# vds_topboard_beaglebone_revA.net
KiCad netlist of a schematic drawn in EAGLE
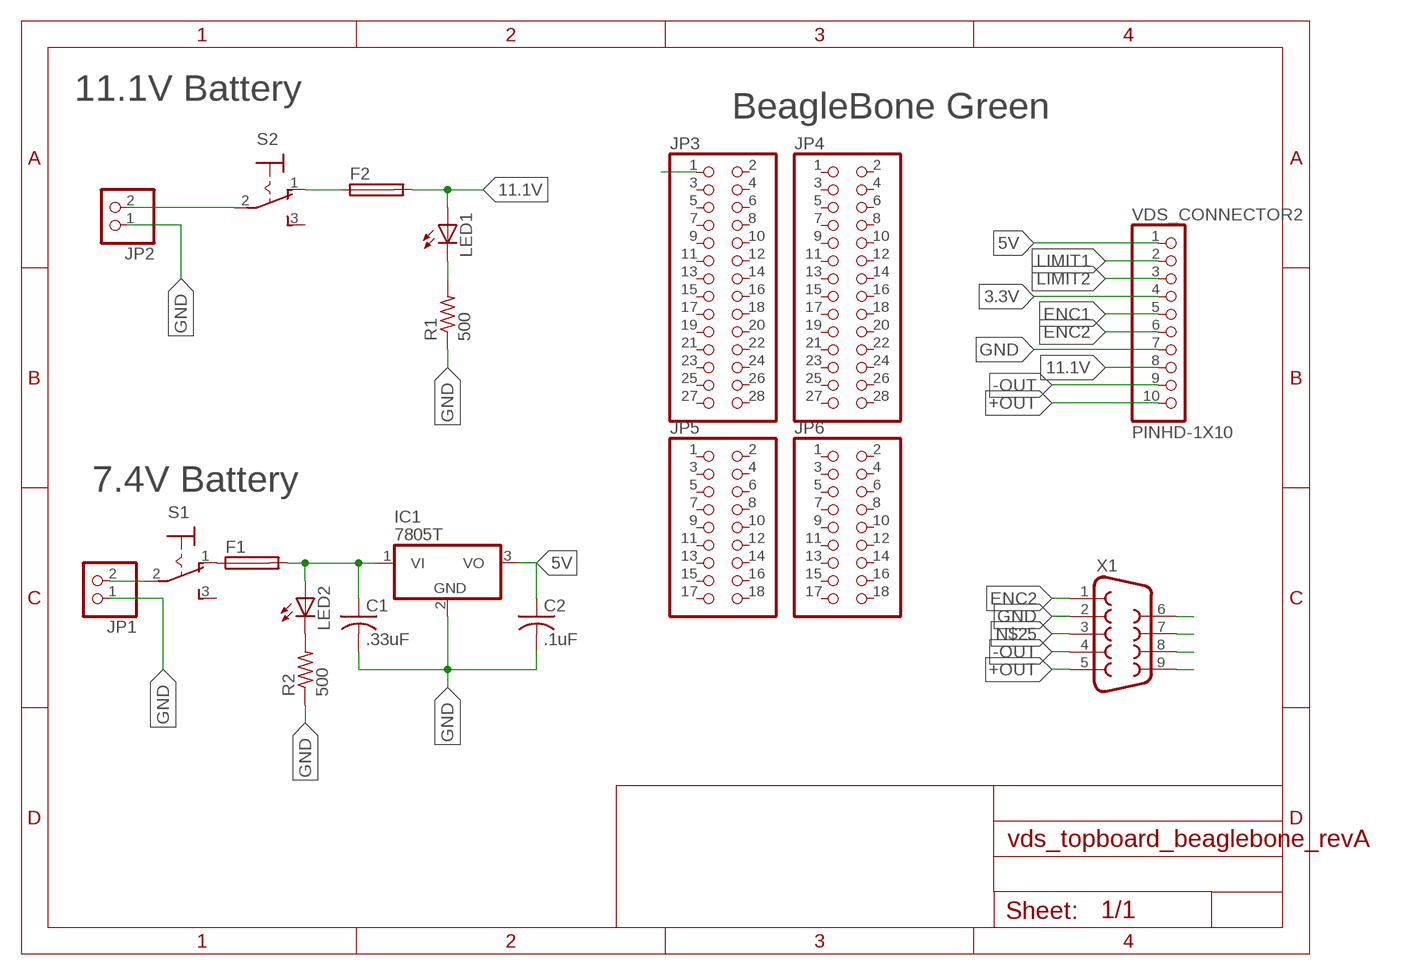
[diagram p0: schematic, sheet 1]

(export (version "E")
  (design (tool "Eeschema 10.0.6"))
  (components
    (comp (ref "C1")
      (value ".33uF")
      (footprint "eagle-import:C025-030X050")
      (libsource (lib "eagle-import") (part "C-US025-030X050"))
    )
    (comp (ref "C2")
      (value ".1uF")
      (footprint "eagle-import:C025-030X050")
      (libsource (lib "eagle-import") (part "C-US025-030X050"))
    )
    (comp (ref "F1")
      (value "SH22,5")
      (footprint "eagle-import:SH22,5")
      (fields (field (name "MF") "SCHURTER") (field (name "MPN") "0031.8201"))
      (libsource (lib "eagle-import") (part "SH22,5"))
    )
    (comp (ref "F2")
      (value "SH22,5")
      (footprint "eagle-import:SH22,5")
      (fields (field (name "MF") "SCHURTER") (field (name "MPN") "0031.8201"))
      (libsource (lib "eagle-import") (part "SH22,5"))
    )
    (comp (ref "IC1")
      (value "7805T")
      (footprint "eagle-import:TO220H")
      (libsource (lib "eagle-import") (part "78T05"))
    )
    (comp (ref "JP1")
      (value "PINHD-1X2")
      (footprint "eagle-import:1X02")
      (libsource (lib "eagle-import") (part "PINHD-1X2"))
    )
    (comp (ref "JP2")
      (value "PINHD-1X2")
      (footprint "eagle-import:1X02")
      (libsource (lib "eagle-import") (part "PINHD-1X2"))
    )
    (comp (ref "JP3")
      (value "PINHD-2X14")
      (footprint "eagle-import:2X14")
      (libsource (lib "eagle-import") (part "PINHD-2X14"))
    )
    (comp (ref "JP4")
      (value "PINHD-2X14")
      (footprint "eagle-import:2X14")
      (libsource (lib "eagle-import") (part "PINHD-2X14"))
    )
    (comp (ref "JP5")
      (value "PINHD-2X9-BIG")
      (footprint "eagle-import:2X09-BIG")
      (libsource (lib "eagle-import") (part "PINHD-2X9-BIG"))
    )
    (comp (ref "JP6")
      (value "PINHD-2X9-BIG")
      (footprint "eagle-import:2X09-BIG")
      (libsource (lib "eagle-import") (part "PINHD-2X9-BIG"))
    )
    (comp (ref "LED1")
      (value "LED5MM")
      (footprint "eagle-import:LED5MM")
      (libsource (lib "eagle-import") (part "LED5MM"))
    )
    (comp (ref "LED2")
      (value "LED5MM")
      (footprint "eagle-import:LED5MM")
      (libsource (lib "eagle-import") (part "LED5MM"))
    )
    (comp (ref "R1")
      (value "500")
      (footprint "eagle-import:0204_5")
      (libsource (lib "eagle-import") (part "R-US_0204/5"))
    )
    (comp (ref "R2")
      (value "500")
      (footprint "eagle-import:0204_5")
      (libsource (lib "eagle-import") (part "R-US_0204/5"))
    )
    (comp (ref "S1")
      (value "320-916")
      (footprint "eagle-import:320-916")
      (libsource (lib "eagle-import") (part "320-916"))
    )
    (comp (ref "S2")
      (value "320-916")
      (footprint "eagle-import:320-916")
      (libsource (lib "eagle-import") (part "320-916"))
    )
    (comp (ref "VDS_CONNECTOR2")
      (value "PINHD-1X10")
      (footprint "eagle-import:1X10-BIG")
      (libsource (lib "eagle-import") (part "PINHD-1X10"))
    )
    (comp (ref "X1")
      (value "F09VP")
      (footprint "eagle-import:F09VP")
      (libsource (lib "eagle-import") (part "F09VP"))
    )
  )
  (nets
    (net (code "1") (name "+OUT") (class "Default")
      (node (ref "VDS_CONNECTOR2") (pin "10") (pinfunction "10_10") (pintype "passive"))
      (node (ref "X1") (pin "5") (pinfunction "5_5") (pintype "passive"))
    )
    (net (code "2") (name "-OUT") (class "Default")
      (node (ref "VDS_CONNECTOR2") (pin "9") (pinfunction "9_9") (pintype "passive"))
      (node (ref "X1") (pin "4") (pinfunction "4_4") (pintype "passive"))
    )
    (net (code "3") (name "3.3V") (class "Default")
      (node (ref "VDS_CONNECTOR2") (pin "4") (pinfunction "4_4") (pintype "passive"))
      (node (ref "X1") (pin "7") (pinfunction "7_7") (pintype "passive"))
    )
    (net (code "4") (name "5V") (class "Default")
      (node (ref "C2") (pin "1") (pinfunction "1_1") (pintype "passive"))
      (node (ref "IC1") (pin "3") (pinfunction "VO_3") (pintype "passive"))
      (node (ref "VDS_CONNECTOR2") (pin "1") (pinfunction "1_1") (pintype "passive"))
    )
    (net (code "5") (name "11.1V") (class "Default")
      (node (ref "F2") (pin "2") (pinfunction "2_2") (pintype "passive"))
      (node (ref "LED1") (pin "A") (pinfunction "A_A") (pintype "passive"))
      (node (ref "VDS_CONNECTOR2") (pin "8") (pinfunction "8_8") (pintype "passive"))
    )
    (net (code "6") (name "ENC1") (class "Default")
      (node (ref "VDS_CONNECTOR2") (pin "5") (pinfunction "5_5") (pintype "passive"))
      (node (ref "X1") (pin "6") (pinfunction "6_6") (pintype "passive"))
    )
    (net (code "7") (name "ENC2") (class "Default")
      (node (ref "VDS_CONNECTOR2") (pin "6") (pinfunction "6_6") (pintype "passive"))
      (node (ref "X1") (pin "1") (pinfunction "1_1") (pintype "passive"))
    )
    (net (code "8") (name "GND") (class "Default")
      (node (ref "C1") (pin "2") (pinfunction "2_2") (pintype "passive"))
      (node (ref "C2") (pin "2") (pinfunction "2_2") (pintype "passive"))
      (node (ref "IC1") (pin "2") (pinfunction "GND_2") (pintype "passive"))
      (node (ref "JP1") (pin "1") (pinfunction "1_1") (pintype "passive"))
      (node (ref "JP2") (pin "1") (pinfunction "1_1") (pintype "passive"))
      (node (ref "JP3") (pin "1") (pinfunction "1_1") (pintype "passive"))
      (node (ref "R1") (pin "1") (pinfunction "1_1") (pintype "passive"))
      (node (ref "R2") (pin "1") (pinfunction "1_1") (pintype "passive"))
      (node (ref "VDS_CONNECTOR2") (pin "7") (pinfunction "7_7") (pintype "passive"))
      (node (ref "X1") (pin "2") (pinfunction "2_2") (pintype "passive"))
    )
    (net (code "9") (name "LIMIT1") (class "Default")
      (node (ref "VDS_CONNECTOR2") (pin "2") (pinfunction "2_2") (pintype "passive"))
      (node (ref "X1") (pin "9") (pinfunction "9_9") (pintype "passive"))
    )
    (net (code "10") (name "LIMIT2") (class "Default")
      (node (ref "VDS_CONNECTOR2") (pin "3") (pinfunction "3_3") (pintype "passive"))
      (node (ref "X1") (pin "8") (pinfunction "8_8") (pintype "passive"))
    )
    (net (code "11") (name "N$25") (class "Default")
      (node (ref "X1") (pin "3") (pinfunction "3_3") (pintype "passive"))
    )
    (net (code "12") (name "Net-(IC1-VI)") (class "Default")
      (node (ref "C1") (pin "1") (pinfunction "1_1") (pintype "passive"))
      (node (ref "F1") (pin "2") (pinfunction "2_2") (pintype "passive"))
      (node (ref "IC1") (pin "1") (pinfunction "VI_1") (pintype "input"))
      (node (ref "LED2") (pin "A") (pinfunction "A_A") (pintype "passive"))
    )
    (net (code "13") (name "Net-(LED1-C)") (class "Default")
      (node (ref "LED1") (pin "K") (pinfunction "C_K") (pintype "passive"))
      (node (ref "R1") (pin "2") (pinfunction "2_2") (pintype "passive"))
    )
    (net (code "14") (name "Net-(LED2-C)") (class "Default")
      (node (ref "LED2") (pin "K") (pinfunction "C_K") (pintype "passive"))
      (node (ref "R2") (pin "2") (pinfunction "2_2") (pintype "passive"))
    )
    (net (code "15") (name "Net-(S1-O)") (class "Default")
      (node (ref "F1") (pin "1") (pinfunction "1_1") (pintype "passive"))
      (node (ref "S1") (pin "1") (pinfunction "O_1") (pintype "passive"))
    )
    (net (code "16") (name "Net-(S1-P)") (class "Default")
      (node (ref "JP1") (pin "2") (pinfunction "2_2") (pintype "passive"))
      (node (ref "S1") (pin "2") (pinfunction "P_2") (pintype "passive"))
    )
    (net (code "17") (name "Net-(S2-O)") (class "Default")
      (node (ref "F2") (pin "1") (pinfunction "1_1") (pintype "passive"))
      (node (ref "S2") (pin "1") (pinfunction "O_1") (pintype "passive"))
    )
    (net (code "18") (name "Net-(S2-P)") (class "Default")
      (node (ref "JP2") (pin "2") (pinfunction "2_2") (pintype "passive"))
      (node (ref "S2") (pin "2") (pinfunction "P_2") (pintype "passive"))
    )
    (net (code "19") (name "unconnected-(JP3-Pad2)") (class "Default")
      (node (ref "JP3") (pin "2") (pinfunction "2_2") (pintype "passive"))
    )
    (net (code "20") (name "unconnected-(JP3-Pad3)") (class "Default")
      (node (ref "JP3") (pin "3") (pinfunction "3_3") (pintype "passive"))
    )
    (net (code "21") (name "unconnected-(JP3-Pad4)") (class "Default")
      (node (ref "JP3") (pin "4") (pinfunction "4_4") (pintype "passive"))
    )
    (net (code "22") (name "unconnected-(JP3-Pad5)") (class "Default")
      (node (ref "JP3") (pin "5") (pinfunction "5_5") (pintype "passive"))
    )
    (net (code "23") (name "unconnected-(JP3-Pad6)") (class "Default")
      (node (ref "JP3") (pin "6") (pinfunction "6_6") (pintype "passive"))
    )
    (net (code "24") (name "unconnected-(JP3-Pad7)") (class "Default")
      (node (ref "JP3") (pin "7") (pinfunction "7_7") (pintype "passive"))
    )
    (net (code "25") (name "unconnected-(JP3-Pad8)") (class "Default")
      (node (ref "JP3") (pin "8") (pinfunction "8_8") (pintype "passive"))
    )
    (net (code "26") (name "unconnected-(JP3-Pad9)") (class "Default")
      (node (ref "JP3") (pin "9") (pinfunction "9_9") (pintype "passive"))
    )
    (net (code "27") (name "unconnected-(JP3-Pad10)") (class "Default")
      (node (ref "JP3") (pin "10") (pinfunction "10_10") (pintype "passive"))
    )
    (net (code "28") (name "unconnected-(JP3-Pad11)") (class "Default")
      (node (ref "JP3") (pin "11") (pinfunction "11_11") (pintype "passive"))
    )
    (net (code "29") (name "unconnected-(JP3-Pad12)") (class "Default")
      (node (ref "JP3") (pin "12") (pinfunction "12_12") (pintype "passive"))
    )
    (net (code "30") (name "unconnected-(JP3-Pad13)") (class "Default")
      (node (ref "JP3") (pin "13") (pinfunction "13_13") (pintype "passive"))
    )
    (net (code "31") (name "unconnected-(JP3-Pad14)") (class "Default")
      (node (ref "JP3") (pin "14") (pinfunction "14_14") (pintype "passive"))
    )
    (net (code "32") (name "unconnected-(JP3-Pad15)") (class "Default")
      (node (ref "JP3") (pin "15") (pinfunction "15_15") (pintype "passive"))
    )
    (net (code "33") (name "unconnected-(JP3-Pad16)") (class "Default")
      (node (ref "JP3") (pin "16") (pinfunction "16_16") (pintype "passive"))
    )
    (net (code "34") (name "unconnected-(JP3-Pad17)") (class "Default")
      (node (ref "JP3") (pin "17") (pinfunction "17_17") (pintype "passive"))
    )
    (net (code "35") (name "unconnected-(JP3-Pad18)") (class "Default")
      (node (ref "JP3") (pin "18") (pinfunction "18_18") (pintype "passive"))
    )
    (net (code "36") (name "unconnected-(JP3-Pad19)") (class "Default")
      (node (ref "JP3") (pin "19") (pinfunction "19_19") (pintype "passive"))
    )
    (net (code "37") (name "unconnected-(JP3-Pad20)") (class "Default")
      (node (ref "JP3") (pin "20") (pinfunction "20_20") (pintype "passive"))
    )
    (net (code "38") (name "unconnected-(JP3-Pad21)") (class "Default")
      (node (ref "JP3") (pin "21") (pinfunction "21_21") (pintype "passive"))
    )
    (net (code "39") (name "unconnected-(JP3-Pad22)") (class "Default")
      (node (ref "JP3") (pin "22") (pinfunction "22_22") (pintype "passive"))
    )
    (net (code "40") (name "unconnected-(JP3-Pad23)") (class "Default")
      (node (ref "JP3") (pin "23") (pinfunction "23_23") (pintype "passive"))
    )
    (net (code "41") (name "unconnected-(JP3-Pad24)") (class "Default")
      (node (ref "JP3") (pin "24") (pinfunction "24_24") (pintype "passive"))
    )
    (net (code "42") (name "unconnected-(JP3-Pad25)") (class "Default")
      (node (ref "JP3") (pin "25") (pinfunction "25_25") (pintype "passive"))
    )
    (net (code "43") (name "unconnected-(JP3-Pad26)") (class "Default")
      (node (ref "JP3") (pin "26") (pinfunction "26_26") (pintype "passive"))
    )
    (net (code "44") (name "unconnected-(JP3-Pad27)") (class "Default")
      (node (ref "JP3") (pin "27") (pinfunction "27_27") (pintype "passive"))
    )
    (net (code "45") (name "unconnected-(JP3-Pad28)") (class "Default")
      (node (ref "JP3") (pin "28") (pinfunction "28_28") (pintype "passive"))
    )
    (net (code "46") (name "unconnected-(JP4-Pad1)") (class "Default")
      (node (ref "JP4") (pin "1") (pinfunction "1_1") (pintype "passive"))
    )
    (net (code "47") (name "unconnected-(JP4-Pad2)") (class "Default")
      (node (ref "JP4") (pin "2") (pinfunction "2_2") (pintype "passive"))
    )
    (net (code "48") (name "unconnected-(JP4-Pad3)") (class "Default")
      (node (ref "JP4") (pin "3") (pinfunction "3_3") (pintype "passive"))
    )
    (net (code "49") (name "unconnected-(JP4-Pad4)") (class "Default")
      (node (ref "JP4") (pin "4") (pinfunction "4_4") (pintype "passive"))
    )
    (net (code "50") (name "unconnected-(JP4-Pad5)") (class "Default")
      (node (ref "JP4") (pin "5") (pinfunction "5_5") (pintype "passive"))
    )
    (net (code "51") (name "unconnected-(JP4-Pad6)") (class "Default")
      (node (ref "JP4") (pin "6") (pinfunction "6_6") (pintype "passive"))
    )
    (net (code "52") (name "unconnected-(JP4-Pad7)") (class "Default")
      (node (ref "JP4") (pin "7") (pinfunction "7_7") (pintype "passive"))
    )
    (net (code "53") (name "unconnected-(JP4-Pad8)") (class "Default")
      (node (ref "JP4") (pin "8") (pinfunction "8_8") (pintype "passive"))
    )
    (net (code "54") (name "unconnected-(JP4-Pad9)") (class "Default")
      (node (ref "JP4") (pin "9") (pinfunction "9_9") (pintype "passive"))
    )
    (net (code "55") (name "unconnected-(JP4-Pad10)") (class "Default")
      (node (ref "JP4") (pin "10") (pinfunction "10_10") (pintype "passive"))
    )
    (net (code "56") (name "unconnected-(JP4-Pad11)") (class "Default")
      (node (ref "JP4") (pin "11") (pinfunction "11_11") (pintype "passive"))
    )
    (net (code "57") (name "unconnected-(JP4-Pad12)") (class "Default")
      (node (ref "JP4") (pin "12") (pinfunction "12_12") (pintype "passive"))
    )
    (net (code "58") (name "unconnected-(JP4-Pad13)") (class "Default")
      (node (ref "JP4") (pin "13") (pinfunction "13_13") (pintype "passive"))
    )
    (net (code "59") (name "unconnected-(JP4-Pad14)") (class "Default")
      (node (ref "JP4") (pin "14") (pinfunction "14_14") (pintype "passive"))
    )
    (net (code "60") (name "unconnected-(JP4-Pad15)") (class "Default")
      (node (ref "JP4") (pin "15") (pinfunction "15_15") (pintype "passive"))
    )
    (net (code "61") (name "unconnected-(JP4-Pad16)") (class "Default")
      (node (ref "JP4") (pin "16") (pinfunction "16_16") (pintype "passive"))
    )
    (net (code "62") (name "unconnected-(JP4-Pad17)") (class "Default")
      (node (ref "JP4") (pin "17") (pinfunction "17_17") (pintype "passive"))
    )
    (net (code "63") (name "unconnected-(JP4-Pad18)") (class "Default")
      (node (ref "JP4") (pin "18") (pinfunction "18_18") (pintype "passive"))
    )
    (net (code "64") (name "unconnected-(JP4-Pad19)") (class "Default")
      (node (ref "JP4") (pin "19") (pinfunction "19_19") (pintype "passive"))
    )
    (net (code "65") (name "unconnected-(JP4-Pad20)") (class "Default")
      (node (ref "JP4") (pin "20") (pinfunction "20_20") (pintype "passive"))
    )
    (net (code "66") (name "unconnected-(JP4-Pad21)") (class "Default")
      (node (ref "JP4") (pin "21") (pinfunction "21_21") (pintype "passive"))
    )
    (net (code "67") (name "unconnected-(JP4-Pad22)") (class "Default")
      (node (ref "JP4") (pin "22") (pinfunction "22_22") (pintype "passive"))
    )
    (net (code "68") (name "unconnected-(JP4-Pad23)") (class "Default")
      (node (ref "JP4") (pin "23") (pinfunction "23_23") (pintype "passive"))
    )
    (net (code "69") (name "unconnected-(JP4-Pad24)") (class "Default")
      (node (ref "JP4") (pin "24") (pinfunction "24_24") (pintype "passive"))
    )
    (net (code "70") (name "unconnected-(JP4-Pad25)") (class "Default")
      (node (ref "JP4") (pin "25") (pinfunction "25_25") (pintype "passive"))
    )
    (net (code "71") (name "unconnected-(JP4-Pad26)") (class "Default")
      (node (ref "JP4") (pin "26") (pinfunction "26_26") (pintype "passive"))
    )
    (net (code "72") (name "unconnected-(JP4-Pad27)") (class "Default")
      (node (ref "JP4") (pin "27") (pinfunction "27_27") (pintype "passive"))
    )
    (net (code "73") (name "unconnected-(JP4-Pad28)") (class "Default")
      (node (ref "JP4") (pin "28") (pinfunction "28_28") (pintype "passive"))
    )
    (net (code "74") (name "unconnected-(JP5-Pad1)") (class "Default")
      (node (ref "JP5") (pin "1") (pinfunction "1_1") (pintype "passive"))
    )
    (net (code "75") (name "unconnected-(JP5-Pad2)") (class "Default")
      (node (ref "JP5") (pin "2") (pinfunction "2_2") (pintype "passive"))
    )
    (net (code "76") (name "unconnected-(JP5-Pad3)") (class "Default")
      (node (ref "JP5") (pin "3") (pinfunction "3_3") (pintype "passive"))
    )
    (net (code "77") (name "unconnected-(JP5-Pad4)") (class "Default")
      (node (ref "JP5") (pin "4") (pinfunction "4_4") (pintype "passive"))
    )
    (net (code "78") (name "unconnected-(JP5-Pad5)") (class "Default")
      (node (ref "JP5") (pin "5") (pinfunction "5_5") (pintype "passive"))
    )
    (net (code "79") (name "unconnected-(JP5-Pad6)") (class "Default")
      (node (ref "JP5") (pin "6") (pinfunction "6_6") (pintype "passive"))
    )
    (net (code "80") (name "unconnected-(JP5-Pad7)") (class "Default")
      (node (ref "JP5") (pin "7") (pinfunction "7_7") (pintype "passive"))
    )
    (net (code "81") (name "unconnected-(JP5-Pad8)") (class "Default")
      (node (ref "JP5") (pin "8") (pinfunction "8_8") (pintype "passive"))
    )
    (net (code "82") (name "unconnected-(JP5-Pad9)") (class "Default")
      (node (ref "JP5") (pin "9") (pinfunction "9_9") (pintype "passive"))
    )
    (net (code "83") (name "unconnected-(JP5-Pad10)") (class "Default")
      (node (ref "JP5") (pin "10") (pinfunction "10_10") (pintype "passive"))
    )
    (net (code "84") (name "unconnected-(JP5-Pad11)") (class "Default")
      (node (ref "JP5") (pin "11") (pinfunction "11_11") (pintype "passive"))
    )
    (net (code "85") (name "unconnected-(JP5-Pad12)") (class "Default")
      (node (ref "JP5") (pin "12") (pinfunction "12_12") (pintype "passive"))
    )
    (net (code "86") (name "unconnected-(JP5-Pad13)") (class "Default")
      (node (ref "JP5") (pin "13") (pinfunction "13_13") (pintype "passive"))
    )
    (net (code "87") (name "unconnected-(JP5-Pad14)") (class "Default")
      (node (ref "JP5") (pin "14") (pinfunction "14_14") (pintype "passive"))
    )
    (net (code "88") (name "unconnected-(JP5-Pad15)") (class "Default")
      (node (ref "JP5") (pin "15") (pinfunction "15_15") (pintype "passive"))
    )
    (net (code "89") (name "unconnected-(JP5-Pad16)") (class "Default")
      (node (ref "JP5") (pin "16") (pinfunction "16_16") (pintype "passive"))
    )
    (net (code "90") (name "unconnected-(JP5-Pad17)") (class "Default")
      (node (ref "JP5") (pin "17") (pinfunction "17_17") (pintype "passive"))
    )
    (net (code "91") (name "unconnected-(JP5-Pad18)") (class "Default")
      (node (ref "JP5") (pin "18") (pinfunction "18_18") (pintype "passive"))
    )
    (net (code "92") (name "unconnected-(JP6-Pad1)") (class "Default")
      (node (ref "JP6") (pin "1") (pinfunction "1_1") (pintype "passive"))
    )
    (net (code "93") (name "unconnected-(JP6-Pad2)") (class "Default")
      (node (ref "JP6") (pin "2") (pinfunction "2_2") (pintype "passive"))
    )
    (net (code "94") (name "unconnected-(JP6-Pad3)") (class "Default")
      (node (ref "JP6") (pin "3") (pinfunction "3_3") (pintype "passive"))
    )
    (net (code "95") (name "unconnected-(JP6-Pad4)") (class "Default")
      (node (ref "JP6") (pin "4") (pinfunction "4_4") (pintype "passive"))
    )
    (net (code "96") (name "unconnected-(JP6-Pad5)") (class "Default")
      (node (ref "JP6") (pin "5") (pinfunction "5_5") (pintype "passive"))
    )
    (net (code "97") (name "unconnected-(JP6-Pad6)") (class "Default")
      (node (ref "JP6") (pin "6") (pinfunction "6_6") (pintype "passive"))
    )
    (net (code "98") (name "unconnected-(JP6-Pad7)") (class "Default")
      (node (ref "JP6") (pin "7") (pinfunction "7_7") (pintype "passive"))
    )
    (net (code "99") (name "unconnected-(JP6-Pad8)") (class "Default")
      (node (ref "JP6") (pin "8") (pinfunction "8_8") (pintype "passive"))
    )
    (net (code "100") (name "unconnected-(JP6-Pad9)") (class "Default")
      (node (ref "JP6") (pin "9") (pinfunction "9_9") (pintype "passive"))
    )
    (net (code "101") (name "unconnected-(JP6-Pad10)") (class "Default")
      (node (ref "JP6") (pin "10") (pinfunction "10_10") (pintype "passive"))
    )
    (net (code "102") (name "unconnected-(JP6-Pad11)") (class "Default")
      (node (ref "JP6") (pin "11") (pinfunction "11_11") (pintype "passive"))
    )
    (net (code "103") (name "unconnected-(JP6-Pad12)") (class "Default")
      (node (ref "JP6") (pin "12") (pinfunction "12_12") (pintype "passive"))
    )
    (net (code "104") (name "unconnected-(JP6-Pad13)") (class "Default")
      (node (ref "JP6") (pin "13") (pinfunction "13_13") (pintype "passive"))
    )
    (net (code "105") (name "unconnected-(JP6-Pad14)") (class "Default")
      (node (ref "JP6") (pin "14") (pinfunction "14_14") (pintype "passive"))
    )
    (net (code "106") (name "unconnected-(JP6-Pad15)") (class "Default")
      (node (ref "JP6") (pin "15") (pinfunction "15_15") (pintype "passive"))
    )
    (net (code "107") (name "unconnected-(JP6-Pad16)") (class "Default")
      (node (ref "JP6") (pin "16") (pinfunction "16_16") (pintype "passive"))
    )
    (net (code "108") (name "unconnected-(JP6-Pad17)") (class "Default")
      (node (ref "JP6") (pin "17") (pinfunction "17_17") (pintype "passive"))
    )
    (net (code "109") (name "unconnected-(JP6-Pad18)") (class "Default")
      (node (ref "JP6") (pin "18") (pinfunction "18_18") (pintype "passive"))
    )
    (net (code "110") (name "unconnected-(S1-S-Pad3)") (class "Default")
      (node (ref "S1") (pin "3") (pinfunction "S_3") (pintype "passive"))
    )
    (net (code "111") (name "unconnected-(S2-S-Pad3)") (class "Default")
      (node (ref "S2") (pin "3") (pinfunction "S_3") (pintype "passive"))
    )
  )
)
